# mcu_block.net
KiCad netlist of a schematic drawn in EAGLE
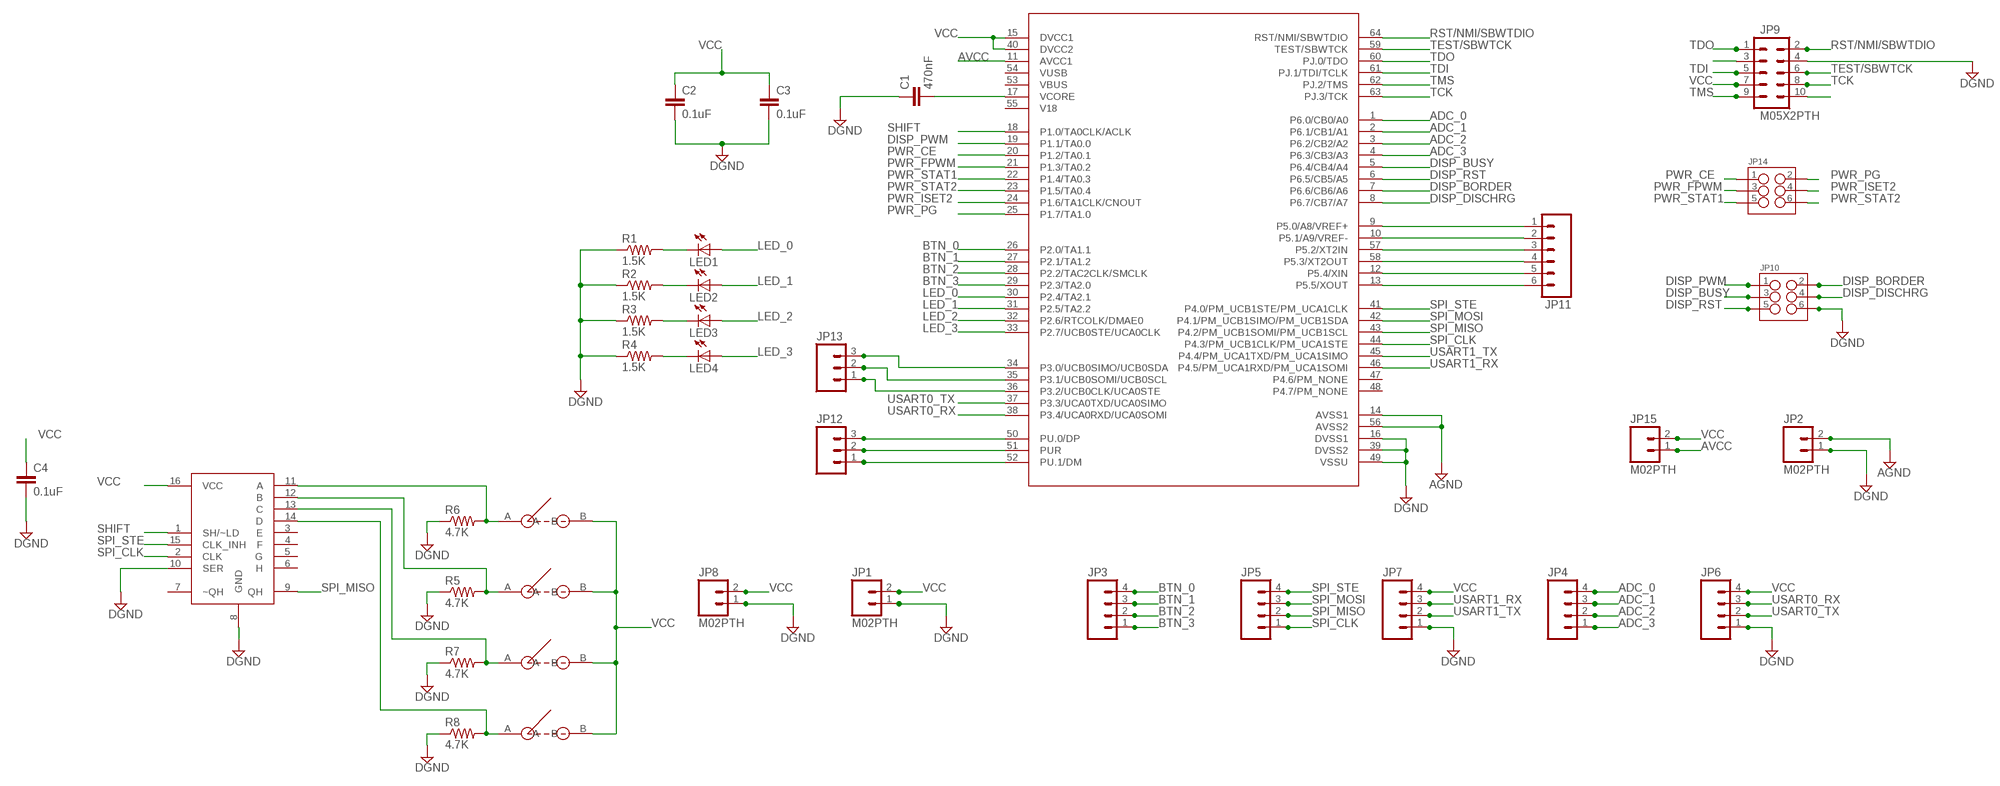
[diagram p0: schematic, sheet 1]

(export (version "E")
  (design (tool "Eeschema 10.0.6"))
  (components
    (comp (ref "C1")
      (value "470nF")
      (footprint "eagle-import:0603-CAP")
      (libsource (lib "eagle-import") (part "CAP0603-CAP"))
    )
    (comp (ref "C2")
      (value "0.1uF")
      (footprint "eagle-import:0603-CAP")
      (libsource (lib "eagle-import") (part "CAP0603-CAP"))
    )
    (comp (ref "C3")
      (value "0.1uF")
      (footprint "eagle-import:0603-CAP")
      (libsource (lib "eagle-import") (part "CAP0603-CAP"))
    )
    (comp (ref "C4")
      (value "0.1uF")
      (footprint "eagle-import:0603-CAP")
      (libsource (lib "eagle-import") (part "CAP0603-CAP"))
    )
    (comp (ref "JP1")
      (value "M02PTH")
      (footprint "eagle-import:1X02")
      (libsource (lib "eagle-import") (part "M02PTH"))
    )
    (comp (ref "JP2")
      (value "M02PTH")
      (footprint "eagle-import:1X02")
      (libsource (lib "eagle-import") (part "M02PTH"))
    )
    (comp (ref "JP3")
      (value "M04LOCK")
      (footprint "eagle-import:1X04_LOCK")
      (libsource (lib "eagle-import") (part "M04LOCK"))
    )
    (comp (ref "JP4")
      (value "M04LOCK")
      (footprint "eagle-import:1X04_LOCK")
      (libsource (lib "eagle-import") (part "M04LOCK"))
    )
    (comp (ref "JP5")
      (value "M04LOCK")
      (footprint "eagle-import:1X04_LOCK")
      (libsource (lib "eagle-import") (part "M04LOCK"))
    )
    (comp (ref "JP6")
      (value "M04LOCK")
      (footprint "eagle-import:1X04_LOCK")
      (libsource (lib "eagle-import") (part "M04LOCK"))
    )
    (comp (ref "JP7")
      (value "M04LOCK")
      (footprint "eagle-import:1X04_LOCK")
      (libsource (lib "eagle-import") (part "M04LOCK"))
    )
    (comp (ref "JP8")
      (value "M02PTH")
      (footprint "eagle-import:1X02")
      (libsource (lib "eagle-import") (part "M02PTH"))
    )
    (comp (ref "JP9")
      (value "M05X2PTH")
      (footprint "eagle-import:AVR_ICSP")
      (libsource (lib "eagle-import") (part "M05X2PTH"))
    )
    (comp (ref "JP10")
      (value "M03X2POGO_PINS")
      (footprint "eagle-import:2X3_POGO")
      (libsource (lib "eagle-import") (part "M03X2POGO_PINS"))
    )
    (comp (ref "JP11")
      (value "M06SIP")
      (footprint "eagle-import:1X06")
      (libsource (lib "eagle-import") (part "M06SIP"))
    )
    (comp (ref "JP12")
      (value "M03PTH")
      (footprint "eagle-import:1X03")
      (libsource (lib "eagle-import") (part "M03PTH"))
    )
    (comp (ref "JP13")
      (value "M03PTH")
      (footprint "eagle-import:1X03")
      (libsource (lib "eagle-import") (part "M03PTH"))
    )
    (comp (ref "JP14")
      (value "M03X2POGO_PINS")
      (footprint "eagle-import:2X3_POGO")
      (libsource (lib "eagle-import") (part "M03X2POGO_PINS"))
    )
    (comp (ref "JP15")
      (value "M02PTH")
      (footprint "eagle-import:1X02")
      (libsource (lib "eagle-import") (part "M02PTH"))
    )
    (comp (ref "LED1")
      (value "LED0603")
      (footprint "eagle-import:LED-0603")
      (libsource (lib "eagle-import") (part "LED0603"))
    )
    (comp (ref "LED2")
      (value "LED0603")
      (footprint "eagle-import:LED-0603")
      (libsource (lib "eagle-import") (part "LED0603"))
    )
    (comp (ref "LED3")
      (value "LED0603")
      (footprint "eagle-import:LED-0603")
      (libsource (lib "eagle-import") (part "LED0603"))
    )
    (comp (ref "LED4")
      (value "LED0603")
      (footprint "eagle-import:LED-0603")
      (libsource (lib "eagle-import") (part "LED0603"))
    )
    (comp (ref "R1")
      (value "1.5K")
      (footprint "eagle-import:0603-RES")
      (libsource (lib "eagle-import") (part "RESISTOR0603-RES"))
    )
    (comp (ref "R2")
      (value "1.5K")
      (footprint "eagle-import:0603-RES")
      (libsource (lib "eagle-import") (part "RESISTOR0603-RES"))
    )
    (comp (ref "R3")
      (value "1.5K")
      (footprint "eagle-import:0603-RES")
      (libsource (lib "eagle-import") (part "RESISTOR0603-RES"))
    )
    (comp (ref "R4")
      (value "1.5K")
      (footprint "eagle-import:0603-RES")
      (libsource (lib "eagle-import") (part "RESISTOR0603-RES"))
    )
    (comp (ref "R5")
      (value "4.7K")
      (footprint "eagle-import:0603-RES")
      (libsource (lib "eagle-import") (part "RESISTOR0603-RES"))
    )
    (comp (ref "R6")
      (value "4.7K")
      (footprint "eagle-import:0603-RES")
      (libsource (lib "eagle-import") (part "RESISTOR0603-RES"))
    )
    (comp (ref "R7")
      (value "4.7K")
      (footprint "eagle-import:0603-RES")
      (libsource (lib "eagle-import") (part "RESISTOR0603-RES"))
    )
    (comp (ref "R8")
      (value "4.7K")
      (footprint "eagle-import:0603-RES")
      (libsource (lib "eagle-import") (part "RESISTOR0603-RES"))
    )
    (comp (ref "U$1")
      (value "MSP430F5528")
      (footprint "eagle-import:VQFN_RGC_64PIN")
      (libsource (lib "eagle-import") (part "MSP430F5528"))
    )
    (comp (ref "U$2")
      (value "EVQ_TAC_BUTTONS")
      (footprint "eagle-import:EVQ-PF_BUTTONS")
      (libsource (lib "eagle-import") (part "EVQ_TAC_BUTTONS"))
    )
    (comp (ref "U$3")
      (value "EVQ_TAC_BUTTONS")
      (footprint "eagle-import:EVQ-PF_BUTTONS")
      (libsource (lib "eagle-import") (part "EVQ_TAC_BUTTONS"))
    )
    (comp (ref "U$4")
      (value "EVQ_TAC_BUTTONS")
      (footprint "eagle-import:EVQ-PF_BUTTONS")
      (libsource (lib "eagle-import") (part "EVQ_TAC_BUTTONS"))
    )
    (comp (ref "U$5")
      (value "EVQ_TAC_BUTTONS")
      (footprint "eagle-import:EVQ-PF_BUTTONS")
      (libsource (lib "eagle-import") (part "EVQ_TAC_BUTTONS"))
    )
    (comp (ref "U$6")
      (value "8B_SHIFT_REG")
      (footprint "eagle-import:TSSOP16")
      (libsource (lib "eagle-import") (part "8B_SHIFT_REG"))
    )
  )
  (nets
    (net (code "1") (name "/ADC_0") (class "Default")
      (node (ref "JP4") (pin "4") (pinfunction "4_4") (pintype "passive"))
      (node (ref "U$1") (pin "1") (pinfunction "P6.0/CB0/A0_1") (pintype "bidirectional"))
    )
    (net (code "2") (name "/ADC_1") (class "Default")
      (node (ref "JP4") (pin "3") (pinfunction "3_3") (pintype "passive"))
      (node (ref "U$1") (pin "2") (pinfunction "P6.1/CB1/A1_2") (pintype "bidirectional"))
    )
    (net (code "3") (name "/ADC_2") (class "Default")
      (node (ref "JP4") (pin "2") (pinfunction "2_2") (pintype "passive"))
      (node (ref "U$1") (pin "3") (pinfunction "P6.2/CB2/A2_3") (pintype "bidirectional"))
    )
    (net (code "4") (name "/ADC_3") (class "Default")
      (node (ref "JP4") (pin "1") (pinfunction "1_1") (pintype "passive"))
      (node (ref "U$1") (pin "4") (pinfunction "P6.3/CB3/A3_4") (pintype "bidirectional"))
    )
    (net (code "5") (name "/AVCC") (class "Default")
      (node (ref "JP15") (pin "1") (pinfunction "1_1") (pintype "passive"))
      (node (ref "U$1") (pin "11") (pinfunction "AVCC1_11") (pintype "bidirectional"))
    )
    (net (code "6") (name "/BTN_0") (class "Default")
      (node (ref "JP3") (pin "4") (pinfunction "4_4") (pintype "passive"))
      (node (ref "U$1") (pin "26") (pinfunction "P2.0/TA1.1_26") (pintype "bidirectional"))
    )
    (net (code "7") (name "/BTN_1") (class "Default")
      (node (ref "JP3") (pin "3") (pinfunction "3_3") (pintype "passive"))
      (node (ref "U$1") (pin "27") (pinfunction "P2.1/TA1.2_27") (pintype "bidirectional"))
    )
    (net (code "8") (name "/BTN_2") (class "Default")
      (node (ref "JP3") (pin "2") (pinfunction "2_2") (pintype "passive"))
      (node (ref "U$1") (pin "28") (pinfunction "P2.2/TAC2CLK/SMCLK_28") (pintype "bidirectional"))
    )
    (net (code "9") (name "/BTN_3") (class "Default")
      (node (ref "JP3") (pin "1") (pinfunction "1_1") (pintype "passive"))
      (node (ref "U$1") (pin "29") (pinfunction "P2.3/TA2.0_29") (pintype "bidirectional"))
    )
    (net (code "10") (name "/DISP_BORDER") (class "Default")
      (node (ref "JP10") (pin "P$2") (pinfunction "2_P$2") (pintype "bidirectional"))
      (node (ref "U$1") (pin "7") (pinfunction "P6.6/CB6/A6_7") (pintype "bidirectional"))
    )
    (net (code "11") (name "/DISP_BUSY") (class "Default")
      (node (ref "JP10") (pin "P$3") (pinfunction "3_P$3") (pintype "bidirectional"))
      (node (ref "U$1") (pin "5") (pinfunction "P6.4/CB4/A4_5") (pintype "bidirectional"))
    )
    (net (code "12") (name "/DISP_DISCHRG") (class "Default")
      (node (ref "JP10") (pin "P$4") (pinfunction "4_P$4") (pintype "bidirectional"))
      (node (ref "U$1") (pin "8") (pinfunction "P6.7/CB7/A7_8") (pintype "bidirectional"))
    )
    (net (code "13") (name "/DISP_PWM") (class "Default")
      (node (ref "JP10") (pin "P$1") (pinfunction "1_P$1") (pintype "bidirectional"))
      (node (ref "U$1") (pin "19") (pinfunction "P1.1/TA0.0_19") (pintype "bidirectional"))
    )
    (net (code "14") (name "/DISP_RST") (class "Default")
      (node (ref "JP10") (pin "P$5") (pinfunction "5_P$5") (pintype "bidirectional"))
      (node (ref "U$1") (pin "6") (pinfunction "P6.5/CB5/A5_6") (pintype "bidirectional"))
    )
    (net (code "15") (name "/LED_0") (class "Default")
      (node (ref "LED1") (pin "A") (pinfunction "A_A") (pintype "passive"))
      (node (ref "U$1") (pin "30") (pinfunction "P2.4/TA2.1_30") (pintype "bidirectional"))
    )
    (net (code "16") (name "/LED_1") (class "Default")
      (node (ref "LED2") (pin "A") (pinfunction "A_A") (pintype "passive"))
      (node (ref "U$1") (pin "31") (pinfunction "P2.5/TA2.2_31") (pintype "bidirectional"))
    )
    (net (code "17") (name "/LED_2") (class "Default")
      (node (ref "LED3") (pin "A") (pinfunction "A_A") (pintype "passive"))
      (node (ref "U$1") (pin "32") (pinfunction "P2.6/RTCOLK/DMAE0_32") (pintype "bidirectional"))
    )
    (net (code "18") (name "/LED_3") (class "Default")
      (node (ref "LED4") (pin "A") (pinfunction "A_A") (pintype "passive"))
      (node (ref "U$1") (pin "33") (pinfunction "P2.7/UCB0STE/UCA0CLK_33") (pintype "bidirectional"))
    )
    (net (code "19") (name "/PWR_CE") (class "Default")
      (node (ref "JP14") (pin "P$1") (pinfunction "1_P$1") (pintype "bidirectional"))
      (node (ref "U$1") (pin "20") (pinfunction "P1.2/TA0.1_20") (pintype "bidirectional"))
    )
    (net (code "20") (name "/PWR_FPWM") (class "Default")
      (node (ref "JP14") (pin "P$3") (pinfunction "3_P$3") (pintype "bidirectional"))
      (node (ref "U$1") (pin "21") (pinfunction "P1.3/TA0.2_21") (pintype "bidirectional"))
    )
    (net (code "21") (name "/PWR_ISET2") (class "Default")
      (node (ref "JP14") (pin "P$4") (pinfunction "4_P$4") (pintype "bidirectional"))
      (node (ref "U$1") (pin "24") (pinfunction "P1.6/TA1CLK/CNOUT_24") (pintype "bidirectional"))
    )
    (net (code "22") (name "/PWR_PG") (class "Default")
      (node (ref "JP14") (pin "P$2") (pinfunction "2_P$2") (pintype "bidirectional"))
      (node (ref "U$1") (pin "25") (pinfunction "P1.7/TA1.0_25") (pintype "bidirectional"))
    )
    (net (code "23") (name "/PWR_STAT1") (class "Default")
      (node (ref "JP14") (pin "P$5") (pinfunction "5_P$5") (pintype "bidirectional"))
      (node (ref "U$1") (pin "22") (pinfunction "P1.4/TA0.3_22") (pintype "bidirectional"))
    )
    (net (code "24") (name "/PWR_STAT2") (class "Default")
      (node (ref "JP14") (pin "P$6") (pinfunction "6_P$6") (pintype "bidirectional"))
      (node (ref "U$1") (pin "23") (pinfunction "P1.5/TA0.4_23") (pintype "bidirectional"))
    )
    (net (code "25") (name "/RST{slash}NMI{slash}SBWTDIO") (class "Default")
      (node (ref "JP9") (pin "2") (pinfunction "2_2") (pintype "passive"))
      (node (ref "U$1") (pin "64") (pinfunction "RST/NMI/SBWTDIO_64") (pintype "bidirectional"))
    )
    (net (code "26") (name "/SHIFT") (class "Default")
      (node (ref "U$1") (pin "18") (pinfunction "P1.0/TA0CLK/ACLK_18") (pintype "bidirectional"))
      (node (ref "U$6") (pin "1") (pinfunction "SH/~{LD}_1") (pintype "bidirectional"))
    )
    (net (code "27") (name "/SPI_CLK") (class "Default")
      (node (ref "JP5") (pin "1") (pinfunction "1_1") (pintype "passive"))
      (node (ref "U$1") (pin "44") (pinfunction "P4.3/PM_UCB1CLK/PM_UCA1STE_44") (pintype "bidirectional"))
      (node (ref "U$6") (pin "2") (pinfunction "CLK_2") (pintype "bidirectional"))
    )
    (net (code "28") (name "/SPI_MISO") (class "Default")
      (node (ref "JP5") (pin "2") (pinfunction "2_2") (pintype "passive"))
      (node (ref "U$1") (pin "43") (pinfunction "P4.2/PM_UCB1SOMI/PM_UCB1SCL_43") (pintype "bidirectional"))
      (node (ref "U$6") (pin "9") (pinfunction "QH_9") (pintype "bidirectional"))
    )
    (net (code "29") (name "/SPI_MOSI") (class "Default")
      (node (ref "JP5") (pin "3") (pinfunction "3_3") (pintype "passive"))
      (node (ref "U$1") (pin "42") (pinfunction "P4.1/PM_UCB1SIMO/PM_UCB1SDA_42") (pintype "bidirectional"))
    )
    (net (code "30") (name "/SPI_STE") (class "Default")
      (node (ref "JP5") (pin "4") (pinfunction "4_4") (pintype "passive"))
      (node (ref "U$1") (pin "41") (pinfunction "P4.0/PM_UCB1STE/PM_UCA1CLK_41") (pintype "bidirectional"))
      (node (ref "U$6") (pin "15") (pinfunction "CLK_INH_15") (pintype "bidirectional"))
    )
    (net (code "31") (name "/TCK") (class "Default")
      (node (ref "JP9") (pin "8") (pinfunction "8_8") (pintype "passive"))
      (node (ref "U$1") (pin "63") (pinfunction "PJ.3/TCK_63") (pintype "bidirectional"))
    )
    (net (code "32") (name "/TDI") (class "Default")
      (node (ref "JP9") (pin "5") (pinfunction "5_5") (pintype "passive"))
      (node (ref "U$1") (pin "61") (pinfunction "PJ.1/TDI/TCLK_61") (pintype "bidirectional"))
    )
    (net (code "33") (name "/TDO") (class "Default")
      (node (ref "JP9") (pin "1") (pinfunction "1_1") (pintype "passive"))
      (node (ref "U$1") (pin "60") (pinfunction "PJ.0/TDO_60") (pintype "bidirectional"))
    )
    (net (code "34") (name "/TEST{slash}SBWTCK") (class "Default")
      (node (ref "JP9") (pin "6") (pinfunction "6_6") (pintype "passive"))
      (node (ref "U$1") (pin "59") (pinfunction "TEST/SBWTCK_59") (pintype "bidirectional"))
    )
    (net (code "35") (name "/TMS") (class "Default")
      (node (ref "JP9") (pin "9") (pinfunction "9_9") (pintype "passive"))
      (node (ref "U$1") (pin "62") (pinfunction "PJ.2/TMS_62") (pintype "bidirectional"))
    )
    (net (code "36") (name "/USART0_RX") (class "Default")
      (node (ref "JP6") (pin "3") (pinfunction "3_3") (pintype "passive"))
      (node (ref "U$1") (pin "38") (pinfunction "P3.4/UCA0RXD/UCA0SOMI_38") (pintype "bidirectional"))
    )
    (net (code "37") (name "/USART0_TX") (class "Default")
      (node (ref "JP6") (pin "2") (pinfunction "2_2") (pintype "passive"))
      (node (ref "U$1") (pin "37") (pinfunction "P3.3/UCA0TXD/UCA0SIMO_37") (pintype "bidirectional"))
    )
    (net (code "38") (name "/USART1_RX") (class "Default")
      (node (ref "JP7") (pin "3") (pinfunction "3_3") (pintype "passive"))
      (node (ref "U$1") (pin "46") (pinfunction "P4.5/PM_UCA1RXD/PM_UCA1SOMI_46") (pintype "bidirectional"))
    )
    (net (code "39") (name "/USART1_TX") (class "Default")
      (node (ref "JP7") (pin "2") (pinfunction "2_2") (pintype "passive"))
      (node (ref "U$1") (pin "45") (pinfunction "P4.4/PM_UCA1TXD/PM_UCA1SIMO_45") (pintype "bidirectional"))
    )
    (net (code "40") (name "/VCC") (class "Default")
      (node (ref "C2") (pin "1") (pinfunction "1_1") (pintype "passive"))
      (node (ref "C3") (pin "1") (pinfunction "1_1") (pintype "passive"))
      (node (ref "C4") (pin "1") (pinfunction "1_1") (pintype "passive"))
      (node (ref "JP1") (pin "2") (pinfunction "2_2") (pintype "passive"))
      (node (ref "JP15") (pin "2") (pinfunction "2_2") (pintype "passive"))
      (node (ref "JP6") (pin "4") (pinfunction "4_4") (pintype "passive"))
      (node (ref "JP7") (pin "4") (pinfunction "4_4") (pintype "passive"))
      (node (ref "JP8") (pin "2") (pinfunction "2_2") (pintype "passive"))
      (node (ref "JP9") (pin "7") (pinfunction "7_7") (pintype "passive"))
      (node (ref "U$1") (pin "15") (pinfunction "DVCC1_15") (pintype "bidirectional"))
      (node (ref "U$1") (pin "40") (pinfunction "DVCC2_40") (pintype "bidirectional"))
      (node (ref "U$2") (pin "B") (pinfunction "B_B") (pintype "bidirectional"))
      (node (ref "U$3") (pin "B") (pinfunction "B_B") (pintype "bidirectional"))
      (node (ref "U$4") (pin "B") (pinfunction "B_B") (pintype "bidirectional"))
      (node (ref "U$5") (pin "B") (pinfunction "B_B") (pintype "bidirectional"))
      (node (ref "U$6") (pin "16") (pinfunction "VCC_16") (pintype "bidirectional"))
    )
    (net (code "41") (name "AGND") (class "Default")
      (node (ref "JP2") (pin "2") (pinfunction "2_2") (pintype "passive"))
      (node (ref "U$1") (pin "14") (pinfunction "AVSS1_14") (pintype "bidirectional"))
      (node (ref "U$1") (pin "56") (pinfunction "AVSS2_56") (pintype "bidirectional"))
    )
    (net (code "42") (name "DGND") (class "Default")
      (node (ref "C1") (pin "1") (pinfunction "1_1") (pintype "passive"))
      (node (ref "C2") (pin "2") (pinfunction "2_2") (pintype "passive"))
      (node (ref "C3") (pin "2") (pinfunction "2_2") (pintype "passive"))
      (node (ref "C4") (pin "2") (pinfunction "2_2") (pintype "passive"))
      (node (ref "JP1") (pin "1") (pinfunction "1_1") (pintype "passive"))
      (node (ref "JP10") (pin "P$6") (pinfunction "6_P$6") (pintype "bidirectional"))
      (node (ref "JP2") (pin "1") (pinfunction "1_1") (pintype "passive"))
      (node (ref "JP6") (pin "1") (pinfunction "1_1") (pintype "passive"))
      (node (ref "JP7") (pin "1") (pinfunction "1_1") (pintype "passive"))
      (node (ref "JP8") (pin "1") (pinfunction "1_1") (pintype "passive"))
      (node (ref "JP9") (pin "4") (pinfunction "4_4") (pintype "passive"))
      (node (ref "R1") (pin "1") (pinfunction "1_1") (pintype "passive"))
      (node (ref "R2") (pin "1") (pinfunction "1_1") (pintype "passive"))
      (node (ref "R3") (pin "1") (pinfunction "1_1") (pintype "passive"))
      (node (ref "R4") (pin "1") (pinfunction "1_1") (pintype "passive"))
      (node (ref "R5") (pin "1") (pinfunction "1_1") (pintype "passive"))
      (node (ref "R6") (pin "1") (pinfunction "1_1") (pintype "passive"))
      (node (ref "R7") (pin "1") (pinfunction "1_1") (pintype "passive"))
      (node (ref "R8") (pin "1") (pinfunction "1_1") (pintype "passive"))
      (node (ref "U$1") (pin "16") (pinfunction "DVSS1_16") (pintype "bidirectional"))
      (node (ref "U$1") (pin "39") (pinfunction "DVSS2_39") (pintype "bidirectional"))
      (node (ref "U$1") (pin "49") (pinfunction "VSSU_49") (pintype "bidirectional"))
      (node (ref "U$6") (pin "10") (pinfunction "SER_10") (pintype "bidirectional"))
      (node (ref "U$6") (pin "8") (pinfunction "GND_8") (pintype "bidirectional"))
    )
    (net (code "43") (name "Net-(LED1-PadC)") (class "Default")
      (node (ref "LED1") (pin "C") (pinfunction "C_C") (pintype "passive"))
      (node (ref "R1") (pin "2") (pinfunction "2_2") (pintype "passive"))
    )
    (net (code "44") (name "Net-(LED2-PadC)") (class "Default")
      (node (ref "LED2") (pin "C") (pinfunction "C_C") (pintype "passive"))
      (node (ref "R2") (pin "2") (pinfunction "2_2") (pintype "passive"))
    )
    (net (code "45") (name "Net-(LED3-PadC)") (class "Default")
      (node (ref "LED3") (pin "C") (pinfunction "C_C") (pintype "passive"))
      (node (ref "R3") (pin "2") (pinfunction "2_2") (pintype "passive"))
    )
    (net (code "46") (name "Net-(LED4-PadC)") (class "Default")
      (node (ref "LED4") (pin "C") (pinfunction "C_C") (pintype "passive"))
      (node (ref "R4") (pin "2") (pinfunction "2_2") (pintype "passive"))
    )
    (net (code "47") (name "Net-(U$1-P3.0{slash}UCB0SIMO{slash}UCB0SDA)") (class "Default")
      (node (ref "JP13") (pin "3") (pinfunction "3_3") (pintype "passive"))
      (node (ref "U$1") (pin "34") (pinfunction "P3.0/UCB0SIMO/UCB0SDA_34") (pintype "bidirectional"))
    )
    (net (code "48") (name "Net-(U$1-P3.1{slash}UCB0SOMI{slash}UCB0SCL)") (class "Default")
      (node (ref "JP13") (pin "2") (pinfunction "2_2") (pintype "passive"))
      (node (ref "U$1") (pin "35") (pinfunction "P3.1/UCB0SOMI/UCB0SCL_35") (pintype "bidirectional"))
    )
    (net (code "49") (name "Net-(U$1-P3.2{slash}UCB0CLK{slash}UCA0STE)") (class "Default")
      (node (ref "JP13") (pin "1") (pinfunction "1_1") (pintype "passive"))
      (node (ref "U$1") (pin "36") (pinfunction "P3.2/UCB0CLK/UCA0STE_36") (pintype "bidirectional"))
    )
    (net (code "50") (name "Net-(U$1-P5.0{slash}A8{slash}VREF+)") (class "Default")
      (node (ref "JP11") (pin "1") (pinfunction "1_1") (pintype "passive"))
      (node (ref "U$1") (pin "9") (pinfunction "P5.0/A8/VREF+_9") (pintype "bidirectional"))
    )
    (net (code "51") (name "Net-(U$1-P5.1{slash}A9{slash}VREF-)") (class "Default")
      (node (ref "JP11") (pin "2") (pinfunction "2_2") (pintype "passive"))
      (node (ref "U$1") (pin "10") (pinfunction "P5.1/A9/VREF-_10") (pintype "bidirectional"))
    )
    (net (code "52") (name "Net-(U$1-P5.2{slash}XT2IN)") (class "Default")
      (node (ref "JP11") (pin "3") (pinfunction "3_3") (pintype "passive"))
      (node (ref "U$1") (pin "57") (pinfunction "P5.2/XT2IN_57") (pintype "bidirectional"))
    )
    (net (code "53") (name "Net-(U$1-P5.3{slash}XT2OUT)") (class "Default")
      (node (ref "JP11") (pin "4") (pinfunction "4_4") (pintype "passive"))
      (node (ref "U$1") (pin "58") (pinfunction "P5.3/XT2OUT_58") (pintype "bidirectional"))
    )
    (net (code "54") (name "Net-(U$1-P5.4{slash}XIN)") (class "Default")
      (node (ref "JP11") (pin "5") (pinfunction "5_5") (pintype "passive"))
      (node (ref "U$1") (pin "12") (pinfunction "P5.4/XIN_12") (pintype "bidirectional"))
    )
    (net (code "55") (name "Net-(U$1-P5.5{slash}XOUT)") (class "Default")
      (node (ref "JP11") (pin "6") (pinfunction "6_6") (pintype "passive"))
      (node (ref "U$1") (pin "13") (pinfunction "P5.5/XOUT_13") (pintype "bidirectional"))
    )
    (net (code "56") (name "Net-(U$1-PU.0{slash}DP)") (class "Default")
      (node (ref "JP12") (pin "3") (pinfunction "3_3") (pintype "passive"))
      (node (ref "U$1") (pin "50") (pinfunction "PU.0/DP_50") (pintype "bidirectional"))
    )
    (net (code "57") (name "Net-(U$1-PU.1{slash}DM)") (class "Default")
      (node (ref "JP12") (pin "1") (pinfunction "1_1") (pintype "passive"))
      (node (ref "U$1") (pin "52") (pinfunction "PU.1/DM_52") (pintype "bidirectional"))
    )
    (net (code "58") (name "Net-(U$1-PUR)") (class "Default")
      (node (ref "JP12") (pin "2") (pinfunction "2_2") (pintype "passive"))
      (node (ref "U$1") (pin "51") (pinfunction "PUR_51") (pintype "bidirectional"))
    )
    (net (code "59") (name "Net-(U$1-VCORE)") (class "Default")
      (node (ref "C1") (pin "2") (pinfunction "2_2") (pintype "passive"))
      (node (ref "U$1") (pin "17") (pinfunction "VCORE_17") (pintype "bidirectional"))
    )
    (net (code "60") (name "Net-(U$6-A)") (class "Default")
      (node (ref "R6") (pin "2") (pinfunction "2_2") (pintype "passive"))
      (node (ref "U$5") (pin "A") (pinfunction "A_A") (pintype "bidirectional"))
      (node (ref "U$6") (pin "11") (pinfunction "A_11") (pintype "bidirectional"))
    )
    (net (code "61") (name "Net-(U$6-B)") (class "Default")
      (node (ref "R5") (pin "2") (pinfunction "2_2") (pintype "passive"))
      (node (ref "U$2") (pin "A") (pinfunction "A_A") (pintype "bidirectional"))
      (node (ref "U$6") (pin "12") (pinfunction "B_12") (pintype "bidirectional"))
    )
    (net (code "62") (name "Net-(U$6-C)") (class "Default")
      (node (ref "R7") (pin "2") (pinfunction "2_2") (pintype "passive"))
      (node (ref "U$3") (pin "A") (pinfunction "A_A") (pintype "bidirectional"))
      (node (ref "U$6") (pin "13") (pinfunction "C_13") (pintype "bidirectional"))
    )
    (net (code "63") (name "Net-(U$6-D)") (class "Default")
      (node (ref "R8") (pin "2") (pinfunction "2_2") (pintype "passive"))
      (node (ref "U$4") (pin "A") (pinfunction "A_A") (pintype "bidirectional"))
      (node (ref "U$6") (pin "14") (pinfunction "D_14") (pintype "bidirectional"))
    )
    (net (code "64") (name "unconnected-(JP9-Pad3)") (class "Default")
      (node (ref "JP9") (pin "3") (pinfunction "3_3") (pintype "passive"))
    )
    (net (code "65") (name "unconnected-(JP9-Pad10)") (class "Default")
      (node (ref "JP9") (pin "10") (pinfunction "10_10") (pintype "passive"))
    )
    (net (code "66") (name "unconnected-(U$1-P4.6{slash}PM_NONE-Pad47)") (class "Default")
      (node (ref "U$1") (pin "47") (pinfunction "P4.6/PM_NONE_47") (pintype "bidirectional"))
    )
    (net (code "67") (name "unconnected-(U$1-P4.7{slash}PM_NONE-Pad48)") (class "Default")
      (node (ref "U$1") (pin "48") (pinfunction "P4.7/PM_NONE_48") (pintype "bidirectional"))
    )
    (net (code "68") (name "unconnected-(U$1-V18-Pad55)") (class "Default")
      (node (ref "U$1") (pin "55") (pinfunction "V18_55") (pintype "bidirectional"))
    )
    (net (code "69") (name "unconnected-(U$1-VBUS-Pad53)") (class "Default")
      (node (ref "U$1") (pin "53") (pinfunction "VBUS_53") (pintype "bidirectional"))
    )
    (net (code "70") (name "unconnected-(U$1-VUSB-Pad54)") (class "Default")
      (node (ref "U$1") (pin "54") (pinfunction "VUSB_54") (pintype "bidirectional"))
    )
    (net (code "71") (name "unconnected-(U$6-E-Pad3)") (class "Default")
      (node (ref "U$6") (pin "3") (pinfunction "E_3") (pintype "bidirectional"))
    )
    (net (code "72") (name "unconnected-(U$6-F-Pad4)") (class "Default")
      (node (ref "U$6") (pin "4") (pinfunction "F_4") (pintype "bidirectional"))
    )
    (net (code "73") (name "unconnected-(U$6-G-Pad5)") (class "Default")
      (node (ref "U$6") (pin "5") (pinfunction "G_5") (pintype "bidirectional"))
    )
    (net (code "74") (name "unconnected-(U$6-H-Pad6)") (class "Default")
      (node (ref "U$6") (pin "6") (pinfunction "H_6") (pintype "bidirectional"))
    )
    (net (code "75") (name "unconnected-(U$6-~{QH}-Pad7)") (class "Default")
      (node (ref "U$6") (pin "7") (pinfunction "~{QH}_7") (pintype "bidirectional"))
    )
  )
)
